# bbf-audio_out.net
KiCad netlist of a schematic drawn in EAGLE
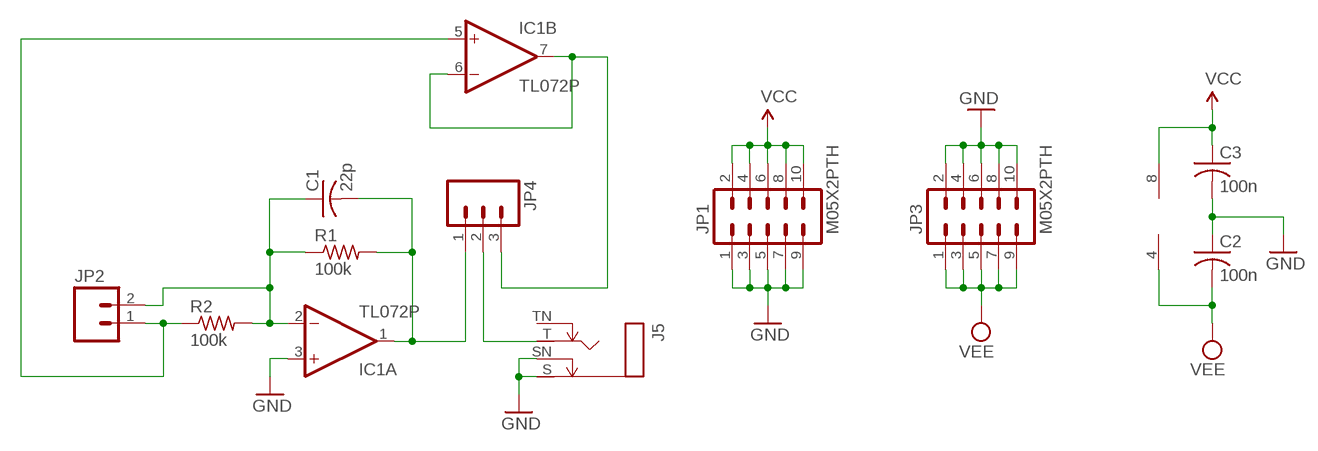
[diagram p0: schematic, sheet 1]

(export (version "E")
  (design (tool "Eeschema 10.0.6"))
  (components
    (comp (ref "C1")
      (value "22p")
      (footprint "eagle-import:C025-025X050")
      (libsource (lib "eagle-import") (part "C-US025-025X050"))
    )
    (comp (ref "C2")
      (value "100n")
      (footprint "eagle-import:C025-025X050")
      (libsource (lib "eagle-import") (part "C-US025-025X050"))
    )
    (comp (ref "C3")
      (value "100n")
      (footprint "eagle-import:C025-025X050")
      (libsource (lib "eagle-import") (part "C-US025-025X050"))
    )
    (comp (ref "IC1")
      (value "TL072P")
      (footprint "eagle-import:DIL08")
      (libsource (lib "eagle-import") (part "TL072P"))
    )
    (comp (ref "J5")
      (value "MONOSWSLIM")
      (footprint "eagle-import:NRJ4HF")
      (libsource (lib "eagle-import") (part "MONOSWSLIM"))
    )
    (comp (ref "JP1")
      (value "M05X2PTH")
      (footprint "eagle-import:AVR_ICSP")
      (libsource (lib "eagle-import") (part "M05X2PTH"))
    )
    (comp (ref "JP2")
      (value "M02PTH")
      (footprint "eagle-import:1X02")
      (libsource (lib "eagle-import") (part "M02PTH"))
    )
    (comp (ref "JP3")
      (value "M05X2PTH")
      (footprint "eagle-import:AVR_ICSP")
      (libsource (lib "eagle-import") (part "M05X2PTH"))
    )
    (comp (ref "JP4")
      (value "M03PTH")
      (footprint "eagle-import:1X03")
      (libsource (lib "eagle-import") (part "M03PTH"))
    )
    (comp (ref "R1")
      (value "100k")
      (footprint "eagle-import:0204_7")
      (libsource (lib "eagle-import") (part "R-US_0204/7"))
    )
    (comp (ref "R2")
      (value "100k")
      (footprint "eagle-import:0204_7")
      (libsource (lib "eagle-import") (part "R-US_0204/7"))
    )
  )
  (nets
    (net (code "1") (name "GND") (class "Default")
      (node (ref "C2") (pin "1") (pinfunction "1_1") (pintype "passive"))
      (node (ref "C3") (pin "2") (pinfunction "2_2") (pintype "passive"))
      (node (ref "IC1") (pin "3") (pinfunction "+IN_3") (pintype "input"))
      (node (ref "J5") (pin "S") (pinfunction "S_S") (pintype "passive"))
      (node (ref "J5") (pin "SN") (pinfunction "SN_SN") (pintype "passive"))
      (node (ref "JP1") (pin "1") (pinfunction "1_1") (pintype "passive"))
      (node (ref "JP1") (pin "3") (pinfunction "3_3") (pintype "passive"))
      (node (ref "JP1") (pin "5") (pinfunction "5_5") (pintype "passive"))
      (node (ref "JP1") (pin "7") (pinfunction "7_7") (pintype "passive"))
      (node (ref "JP1") (pin "9") (pinfunction "9_9") (pintype "passive"))
      (node (ref "JP3") (pin "10") (pinfunction "10_10") (pintype "passive"))
      (node (ref "JP3") (pin "2") (pinfunction "2_2") (pintype "passive"))
      (node (ref "JP3") (pin "4") (pinfunction "4_4") (pintype "passive"))
      (node (ref "JP3") (pin "6") (pinfunction "6_6") (pintype "passive"))
      (node (ref "JP3") (pin "8") (pinfunction "8_8") (pintype "passive"))
    )
    (net (code "2") (name "Net-(IC1A--IN)") (class "Default")
      (node (ref "C1") (pin "1") (pinfunction "1_1") (pintype "passive"))
      (node (ref "IC1") (pin "2") (pinfunction "-IN_2") (pintype "input"))
      (node (ref "JP2") (pin "2") (pinfunction "2_2") (pintype "passive"))
      (node (ref "R1") (pin "1") (pinfunction "1_1") (pintype "passive"))
      (node (ref "R2") (pin "2") (pinfunction "2_2") (pintype "passive"))
    )
    (net (code "3") (name "Net-(IC1A-OUT)") (class "Default")
      (node (ref "C1") (pin "2") (pinfunction "2_2") (pintype "passive"))
      (node (ref "IC1") (pin "1") (pinfunction "OUT_1") (pintype "output"))
      (node (ref "JP4") (pin "1") (pinfunction "1_1") (pintype "passive"))
      (node (ref "R1") (pin "2") (pinfunction "2_2") (pintype "passive"))
    )
    (net (code "4") (name "Net-(IC1B-+IN)") (class "Default")
      (node (ref "IC1") (pin "5") (pinfunction "+IN_5") (pintype "input"))
      (node (ref "JP2") (pin "1") (pinfunction "1_1") (pintype "passive"))
      (node (ref "R2") (pin "1") (pinfunction "1_1") (pintype "passive"))
    )
    (net (code "5") (name "Net-(IC1B--IN)") (class "Default")
      (node (ref "IC1") (pin "6") (pinfunction "-IN_6") (pintype "input"))
      (node (ref "IC1") (pin "7") (pinfunction "OUT_7") (pintype "output"))
      (node (ref "JP4") (pin "3") (pinfunction "3_3") (pintype "passive"))
    )
    (net (code "6") (name "Net-(J5-PadT)") (class "Default")
      (node (ref "J5") (pin "T") (pinfunction "T_T") (pintype "passive"))
      (node (ref "JP4") (pin "2") (pinfunction "2_2") (pintype "passive"))
    )
    (net (code "7") (name "VCC") (class "Default")
      (node (ref "C3") (pin "1") (pinfunction "1_1") (pintype "passive"))
      (node (ref "IC1") (pin "8") (pinfunction "V+_8") (pintype "power_in"))
      (node (ref "JP1") (pin "10") (pinfunction "10_10") (pintype "passive"))
      (node (ref "JP1") (pin "2") (pinfunction "2_2") (pintype "passive"))
      (node (ref "JP1") (pin "4") (pinfunction "4_4") (pintype "passive"))
      (node (ref "JP1") (pin "6") (pinfunction "6_6") (pintype "passive"))
      (node (ref "JP1") (pin "8") (pinfunction "8_8") (pintype "passive"))
    )
    (net (code "8") (name "VEE") (class "Default")
      (node (ref "C2") (pin "2") (pinfunction "2_2") (pintype "passive"))
      (node (ref "IC1") (pin "4") (pinfunction "V-_4") (pintype "power_in"))
      (node (ref "JP3") (pin "1") (pinfunction "1_1") (pintype "passive"))
      (node (ref "JP3") (pin "3") (pinfunction "3_3") (pintype "passive"))
      (node (ref "JP3") (pin "5") (pinfunction "5_5") (pintype "passive"))
      (node (ref "JP3") (pin "7") (pinfunction "7_7") (pintype "passive"))
      (node (ref "JP3") (pin "9") (pinfunction "9_9") (pintype "passive"))
    )
    (net (code "9") (name "unconnected-(J5-PadTN)") (class "Default")
      (node (ref "J5") (pin "TN") (pinfunction "TN_TN") (pintype "passive"))
    )
  )
)
